# RPCamV2_Alt_camera_boardV2.net
KiCad netlist of a schematic drawn in EAGLE
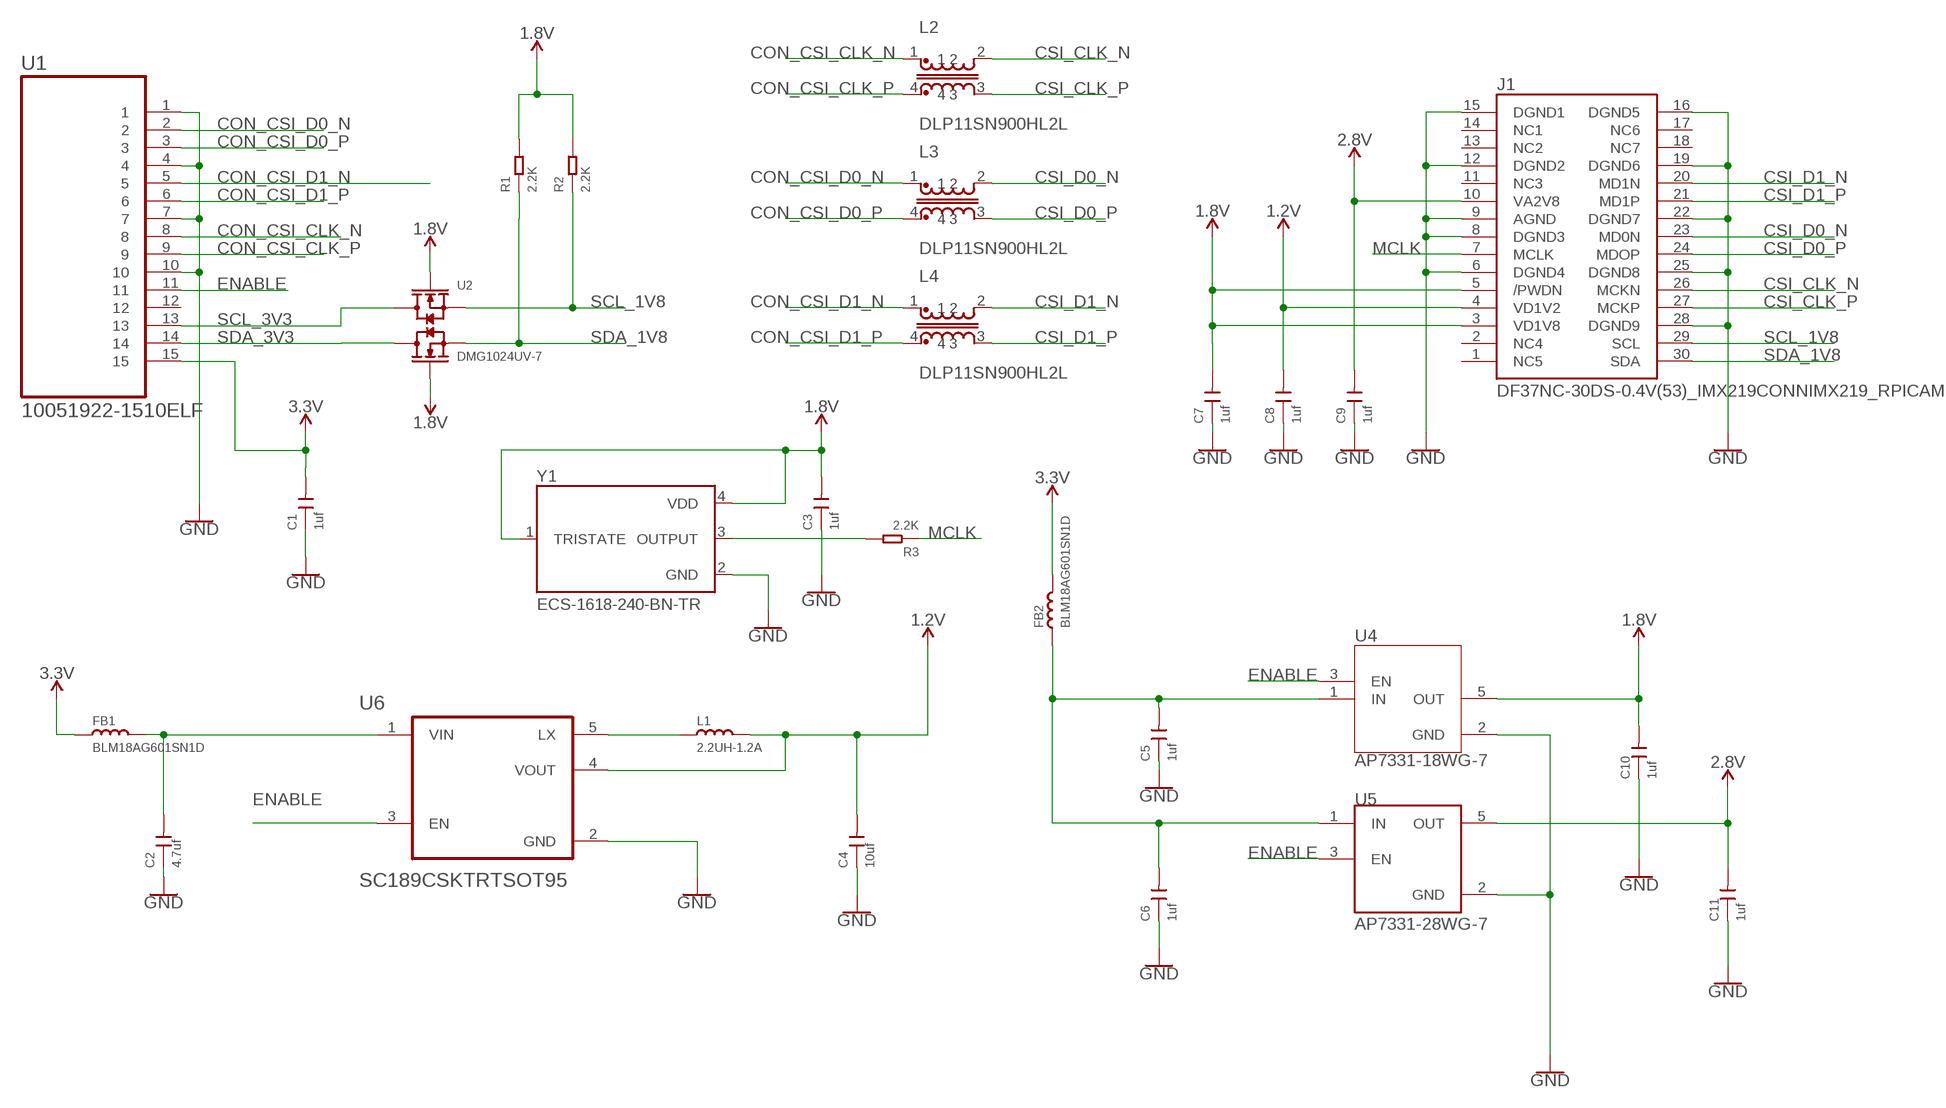
[diagram p0: schematic, sheet 1]

(export (version "E")
  (design (tool "Eeschema 10.0.6"))
  (components
    (comp (ref "C1")
      (value "1uf")
      (footprint "eagle-import:C0402K")
      (fields (field (name "MPN") "MF-CAP-0402-1uF"))
      (libsource (lib "eagle-import") (part "CERAMIC-1UF-10V-10%-X5R(0402)"))
    )
    (comp (ref "C2")
      (value "4.7uf")
      (footprint "eagle-import:C0603")
      (fields (field (name "MPN") "CC0603KRX5R6BB475"))
      (libsource (lib "eagle-import") (part "CERAMIC-4.7UF-10V-10%-X5R(0603)"))
    )
    (comp (ref "C3")
      (value "1uf")
      (footprint "eagle-import:C0402K")
      (fields (field (name "MPN") "MF-CAP-0402-1uF"))
      (libsource (lib "eagle-import") (part "CERAMIC-1UF-10V-10%-X5R(0402)"))
    )
    (comp (ref "C4")
      (value "10uf")
      (footprint "eagle-import:C2012")
      (fields (field (name "MPN") "CC0805KKX5R8BB106"))
      (libsource (lib "eagle-import") (part "CERAMIC-10UF-25V-10%-X5R(0805)"))
    )
    (comp (ref "C5")
      (value "1uf")
      (footprint "eagle-import:C0402K")
      (fields (field (name "MPN") "MF-CAP-0402-1uF"))
      (libsource (lib "eagle-import") (part "CERAMIC-1UF-10V-10%-X5R(0402)"))
    )
    (comp (ref "C6")
      (value "1uf")
      (footprint "eagle-import:C0402K")
      (fields (field (name "MPN") "MF-CAP-0402-1uF"))
      (libsource (lib "eagle-import") (part "CERAMIC-1UF-10V-10%-X5R(0402)"))
    )
    (comp (ref "C7")
      (value "1uf")
      (footprint "eagle-import:C0402K")
      (fields (field (name "MPN") "MF-CAP-0402-1uF"))
      (libsource (lib "eagle-import") (part "CERAMIC-1UF-10V-10%-X5R(0402)"))
    )
    (comp (ref "C8")
      (value "1uf")
      (footprint "eagle-import:C0402K")
      (fields (field (name "MPN") "MF-CAP-0402-1uF"))
      (libsource (lib "eagle-import") (part "CERAMIC-1UF-10V-10%-X5R(0402)"))
    )
    (comp (ref "C9")
      (value "1uf")
      (footprint "eagle-import:C0402K")
      (fields (field (name "MPN") "MF-CAP-0402-1uF"))
      (libsource (lib "eagle-import") (part "CERAMIC-1UF-10V-10%-X5R(0402)"))
    )
    (comp (ref "C10")
      (value "1uf")
      (footprint "eagle-import:C0402K")
      (fields (field (name "MPN") "MF-CAP-0402-1uF"))
      (libsource (lib "eagle-import") (part "CERAMIC-1UF-10V-10%-X5R(0402)"))
    )
    (comp (ref "C11")
      (value "1uf")
      (footprint "eagle-import:C0402K")
      (fields (field (name "MPN") "MF-CAP-0402-1uF"))
      (libsource (lib "eagle-import") (part "CERAMIC-1UF-10V-10%-X5R(0402)"))
    )
    (comp (ref "FB1")
      (value "BLM18AG601SN1D")
      (footprint "eagle-import:BEADC1608X80")
      (libsource (lib "eagle-import") (part "BLM18AG601SN1D"))
    )
    (comp (ref "FB2")
      (value "BLM18AG601SN1D")
      (footprint "eagle-import:BEADC1608X80")
      (libsource (lib "eagle-import") (part "BLM18AG601SN1D"))
    )
    (comp (ref "J1")
      (value "DF37NC-30DS-0.4V(53)_IMX219CONNIMX219_RPICAM")
      (footprint "eagle-import:HRS_DF37NC-30DS-0.4V(53)_IMX219")
      (fields (field (name "MPN") "DF37NC-30DS-0.4V(51)"))
      (libsource (lib "eagle-import") (part "DF37NC-30DS-0.4V(53)_IMX219CONNIMX219_RPICAM"))
    )
    (comp (ref "L1")
      (value "2.2UH-1.2A")
      (footprint "eagle-import:L0805")
      (fields (field (name "MPN") "LQM2MPN2R2MG0"))
      (libsource (lib "eagle-import") (part "SMD-INDUCTOR-2.2UH-20%-1.2A(0805)"))
    )
    (comp (ref "L2")
      (value "DLP11SN900HL2L")
      (footprint "eagle-import:INDC1210X09")
      (fields (field (name "MF") "Murata"))
      (libsource (lib "eagle-import") (part "DLP11SN900HL2L"))
    )
    (comp (ref "L3")
      (value "DLP11SN900HL2L")
      (footprint "eagle-import:INDC1210X09")
      (fields (field (name "MF") "Murata"))
      (libsource (lib "eagle-import") (part "DLP11SN900HL2L"))
    )
    (comp (ref "L4")
      (value "DLP11SN900HL2L")
      (footprint "eagle-import:INDC1210X09")
      (fields (field (name "MF") "Murata"))
      (libsource (lib "eagle-import") (part "DLP11SN900HL2L"))
    )
    (comp (ref "R1")
      (value "2.2K")
      (footprint "eagle-import:R0402")
      (fields (field (name "MPN") "RC0402JR-072K2L"))
      (libsource (lib "eagle-import") (part "SMD-RES-2.2K-5%-1/16W(0402)"))
    )
    (comp (ref "R2")
      (value "2.2K")
      (footprint "eagle-import:R0402")
      (fields (field (name "MPN") "RC0402JR-072K2L"))
      (libsource (lib "eagle-import") (part "SMD-RES-2.2K-5%-1/16W(0402)"))
    )
    (comp (ref "R3")
      (value "2.2K")
      (footprint "eagle-import:R0402")
      (fields (field (name "MPN") "RC0402JR-072K2L"))
      (libsource (lib "eagle-import") (part "SMD-RES-2.2K-5%-1/16W(0402)"))
    )
    (comp (ref "U1")
      (value "10051922-1510ELF")
      (footprint "eagle-import:FCI_10051922-1510ELF")
      (fields (field (name "MF") "FCI"))
      (libsource (lib "eagle-import") (part "10051922-1510ELF"))
    )
    (comp (ref "U2")
      (value "DMG1024UV-7")
      (footprint "eagle-import:SOT50P162X60-6N")
      (fields (field (name "MF") "Diodes Inc."))
      (libsource (lib "eagle-import") (part "DMG1024UV-7"))
    )
    (comp (ref "U4")
      (value "AP7331-18WG-7")
      (footprint "eagle-import:SOT95P285X145-5N")
      (fields (field (name "MF") "Diodes Inc."))
      (libsource (lib "eagle-import") (part "AP7331-18WG-7"))
    )
    (comp (ref "U5")
      (value "AP7331-28WG-7")
      (footprint "eagle-import:SOT95P285X145-5N")
      (fields (field (name "MF") "Diodes Inc."))
      (libsource (lib "eagle-import") (part "AP7331-28WG-7"))
    )
    (comp (ref "U6")
      (value "SC189CSKTRTSOT95")
      (footprint "eagle-import:SOT95P285X145-5N")
      (fields (field (name "MPN") "SC189CSKTRT"))
      (libsource (lib "eagle-import") (part "SC189CSKTRTSOT95"))
    )
    (comp (ref "Y1")
      (value "ECS-1618-240-BN-TR")
      (footprint "eagle-import:XTAL_ECS-1618-060-BN-TR")
      (fields (field (name "DIGI-KEY_PART_NUMBER") "XC1963CT-ND") (field (name "MF") "ECS International"))
      (libsource (lib "eagle-import") (part "ECS-1618-240-BN-TR"))
    )
  )
  (nets
    (net (code "1") (name "/CON_CSI_CLK_N") (class "Default")
      (node (ref "L2") (pin "1") (pinfunction "1_1") (pintype "passive"))
      (node (ref "U1") (pin "8") (pinfunction "8_8") (pintype "passive"))
    )
    (net (code "2") (name "/CON_CSI_CLK_P") (class "Default")
      (node (ref "L2") (pin "4") (pinfunction "4_4") (pintype "passive"))
      (node (ref "U1") (pin "9") (pinfunction "9_9") (pintype "passive"))
    )
    (net (code "3") (name "/CON_CSI_D0_N") (class "Default")
      (node (ref "L3") (pin "1") (pinfunction "1_1") (pintype "passive"))
      (node (ref "U1") (pin "2") (pinfunction "2_2") (pintype "passive"))
    )
    (net (code "4") (name "/CON_CSI_D0_P") (class "Default")
      (node (ref "L3") (pin "4") (pinfunction "4_4") (pintype "passive"))
      (node (ref "U1") (pin "3") (pinfunction "3_3") (pintype "passive"))
    )
    (net (code "5") (name "/CON_CSI_D1_N") (class "Default")
      (node (ref "L4") (pin "1") (pinfunction "1_1") (pintype "passive"))
      (node (ref "U1") (pin "5") (pinfunction "5_5") (pintype "passive"))
    )
    (net (code "6") (name "/CON_CSI_D1_P") (class "Default")
      (node (ref "L4") (pin "4") (pinfunction "4_4") (pintype "passive"))
      (node (ref "U1") (pin "6") (pinfunction "6_6") (pintype "passive"))
    )
    (net (code "7") (name "/CSI_CLK_N") (class "Default")
      (node (ref "J1") (pin "26") (pinfunction "MCKN_26") (pintype "passive"))
      (node (ref "L2") (pin "2") (pinfunction "2_2") (pintype "passive"))
    )
    (net (code "8") (name "/CSI_CLK_P") (class "Default")
      (node (ref "J1") (pin "27") (pinfunction "MCKP_27") (pintype "passive"))
      (node (ref "L2") (pin "3") (pinfunction "3_3") (pintype "passive"))
    )
    (net (code "9") (name "/CSI_D0_N") (class "Default")
      (node (ref "J1") (pin "23") (pinfunction "MD0N_23") (pintype "passive"))
      (node (ref "L3") (pin "2") (pinfunction "2_2") (pintype "passive"))
    )
    (net (code "10") (name "/CSI_D0_P") (class "Default")
      (node (ref "J1") (pin "24") (pinfunction "MDOP_24") (pintype "passive"))
      (node (ref "L3") (pin "3") (pinfunction "3_3") (pintype "passive"))
    )
    (net (code "11") (name "/CSI_D1_N") (class "Default")
      (node (ref "J1") (pin "20") (pinfunction "MD1N_20") (pintype "passive"))
      (node (ref "L4") (pin "2") (pinfunction "2_2") (pintype "passive"))
    )
    (net (code "12") (name "/CSI_D1_P") (class "Default")
      (node (ref "J1") (pin "21") (pinfunction "MD1P_21") (pintype "passive"))
      (node (ref "L4") (pin "3") (pinfunction "3_3") (pintype "passive"))
    )
    (net (code "13") (name "/ENABLE") (class "Default")
      (node (ref "U1") (pin "11") (pinfunction "11_11") (pintype "passive"))
      (node (ref "U4") (pin "3") (pinfunction "EN_3") (pintype "input"))
      (node (ref "U5") (pin "3") (pinfunction "EN_3") (pintype "input"))
      (node (ref "U6") (pin "3") (pinfunction "EN_3") (pintype "input"))
    )
    (net (code "14") (name "/MCLK") (class "Default")
      (node (ref "J1") (pin "7") (pinfunction "MCLK_7") (pintype "passive"))
      (node (ref "R3") (pin "1") (pinfunction "1_1") (pintype "passive"))
    )
    (net (code "15") (name "/SCL_1V8") (class "Default")
      (node (ref "J1") (pin "29") (pinfunction "SCL_29") (pintype "passive"))
      (node (ref "R2") (pin "1") (pinfunction "1_1") (pintype "passive"))
      (node (ref "U2") (pin "S2") (pinfunction "S1_S2") (pintype "passive"))
    )
    (net (code "16") (name "/SCL_3V3") (class "Default")
      (node (ref "U1") (pin "13") (pinfunction "13_13") (pintype "passive"))
      (node (ref "U2") (pin "D2") (pinfunction "D1_D2") (pintype "passive"))
    )
    (net (code "17") (name "/SDA_1V8") (class "Default")
      (node (ref "J1") (pin "30") (pinfunction "SDA_30") (pintype "passive"))
      (node (ref "R1") (pin "1") (pinfunction "1_1") (pintype "passive"))
      (node (ref "U2") (pin "S1") (pinfunction "S0_S1") (pintype "passive"))
    )
    (net (code "18") (name "/SDA_3V3") (class "Default")
      (node (ref "U1") (pin "14") (pinfunction "14_14") (pintype "passive"))
      (node (ref "U2") (pin "D1") (pinfunction "D0_D1") (pintype "passive"))
    )
    (net (code "19") (name "1.2V") (class "Default")
      (node (ref "C4") (pin "2") (pinfunction "2_2") (pintype "passive"))
      (node (ref "C8") (pin "2") (pinfunction "2_2") (pintype "passive"))
      (node (ref "J1") (pin "4") (pinfunction "VD1V2_4") (pintype "passive"))
      (node (ref "L1") (pin "2") (pinfunction "2_2") (pintype "passive"))
      (node (ref "U6") (pin "4") (pinfunction "VOUT_4") (pintype "power_in"))
    )
    (net (code "20") (name "1.8V") (class "Default")
      (node (ref "C10") (pin "2") (pinfunction "2_2") (pintype "passive"))
      (node (ref "C3") (pin "2") (pinfunction "2_2") (pintype "passive"))
      (node (ref "C7") (pin "2") (pinfunction "2_2") (pintype "passive"))
      (node (ref "J1") (pin "3") (pinfunction "VD1V8_3") (pintype "passive"))
      (node (ref "J1") (pin "5") (pinfunction "/PWDN_5") (pintype "passive"))
      (node (ref "R1") (pin "2") (pinfunction "2_2") (pintype "passive"))
      (node (ref "R2") (pin "2") (pinfunction "2_2") (pintype "passive"))
      (node (ref "U2") (pin "G1") (pinfunction "G0_G1") (pintype "passive"))
      (node (ref "U2") (pin "G2") (pinfunction "G1_G2") (pintype "passive"))
      (node (ref "U4") (pin "5") (pinfunction "OUT_5") (pintype "output"))
      (node (ref "Y1") (pin "1") (pinfunction "TRISTATE_1") (pintype "input"))
      (node (ref "Y1") (pin "4") (pinfunction "VDD_4") (pintype "power_in"))
    )
    (net (code "21") (name "2.8V") (class "Default")
      (node (ref "C11") (pin "2") (pinfunction "2_2") (pintype "passive"))
      (node (ref "C9") (pin "2") (pinfunction "2_2") (pintype "passive"))
      (node (ref "J1") (pin "10") (pinfunction "VA2V8_10") (pintype "passive"))
      (node (ref "U5") (pin "5") (pinfunction "OUT_5") (pintype "output"))
    )
    (net (code "22") (name "3.3V") (class "Default")
      (node (ref "C1") (pin "2") (pinfunction "2_2") (pintype "passive"))
      (node (ref "FB1") (pin "1") (pinfunction "1_1") (pintype "passive"))
      (node (ref "FB2") (pin "2") (pinfunction "2_2") (pintype "passive"))
      (node (ref "U1") (pin "15") (pinfunction "15_15") (pintype "passive"))
    )
    (net (code "23") (name "GND") (class "Default")
      (node (ref "C1") (pin "1") (pinfunction "1_1") (pintype "passive"))
      (node (ref "C10") (pin "1") (pinfunction "1_1") (pintype "passive"))
      (node (ref "C11") (pin "1") (pinfunction "1_1") (pintype "passive"))
      (node (ref "C2") (pin "1") (pinfunction "1_1") (pintype "passive"))
      (node (ref "C3") (pin "1") (pinfunction "1_1") (pintype "passive"))
      (node (ref "C4") (pin "1") (pinfunction "1_1") (pintype "passive"))
      (node (ref "C5") (pin "1") (pinfunction "1_1") (pintype "passive"))
      (node (ref "C6") (pin "1") (pinfunction "1_1") (pintype "passive"))
      (node (ref "C7") (pin "1") (pinfunction "1_1") (pintype "passive"))
      (node (ref "C8") (pin "1") (pinfunction "1_1") (pintype "passive"))
      (node (ref "C9") (pin "1") (pinfunction "1_1") (pintype "passive"))
      (node (ref "J1") (pin "12") (pinfunction "DGND2_12") (pintype "passive"))
      (node (ref "J1") (pin "15") (pinfunction "DGND1_15") (pintype "passive"))
      (node (ref "J1") (pin "16") (pinfunction "DGND5_16") (pintype "passive"))
      (node (ref "J1") (pin "19") (pinfunction "DGND6_19") (pintype "passive"))
      (node (ref "J1") (pin "22") (pinfunction "DGND7_22") (pintype "passive"))
      (node (ref "J1") (pin "25") (pinfunction "DGND8_25") (pintype "passive"))
      (node (ref "J1") (pin "28") (pinfunction "DGND9_28") (pintype "passive"))
      (node (ref "J1") (pin "6") (pinfunction "DGND4_6") (pintype "passive"))
      (node (ref "J1") (pin "8") (pinfunction "DGND3_8") (pintype "passive"))
      (node (ref "J1") (pin "9") (pinfunction "AGND_9") (pintype "passive"))
      (node (ref "U1") (pin "1") (pinfunction "1_1") (pintype "passive"))
      (node (ref "U1") (pin "10") (pinfunction "10_10") (pintype "passive"))
      (node (ref "U1") (pin "4") (pinfunction "4_4") (pintype "passive"))
      (node (ref "U1") (pin "7") (pinfunction "7_7") (pintype "passive"))
      (node (ref "U4") (pin "2") (pinfunction "GND_2") (pintype "power_in"))
      (node (ref "U5") (pin "2") (pinfunction "GND_2") (pintype "power_in"))
      (node (ref "U6") (pin "2") (pinfunction "GND_2") (pintype "power_in"))
      (node (ref "Y1") (pin "2") (pinfunction "GND_2") (pintype "power_in"))
    )
    (net (code "24") (name "Net-(U4-IN)") (class "Default")
      (node (ref "C5") (pin "2") (pinfunction "2_2") (pintype "passive"))
      (node (ref "C6") (pin "2") (pinfunction "2_2") (pintype "passive"))
      (node (ref "FB2") (pin "1") (pinfunction "1_1") (pintype "passive"))
      (node (ref "U4") (pin "1") (pinfunction "IN_1") (pintype "input"))
      (node (ref "U5") (pin "1") (pinfunction "IN_1") (pintype "input"))
    )
    (net (code "25") (name "Net-(U6-LX)") (class "Default")
      (node (ref "L1") (pin "1") (pinfunction "1_1") (pintype "passive"))
      (node (ref "U6") (pin "5") (pinfunction "LX_5") (pintype "power_in"))
    )
    (net (code "26") (name "Net-(U6-VIN)") (class "Default")
      (node (ref "C2") (pin "2") (pinfunction "2_2") (pintype "passive"))
      (node (ref "FB1") (pin "2") (pinfunction "2_2") (pintype "passive"))
      (node (ref "U6") (pin "1") (pinfunction "VIN_1") (pintype "power_in"))
    )
    (net (code "27") (name "Net-(Y1-OUTPUT)") (class "Default")
      (node (ref "R3") (pin "2") (pinfunction "2_2") (pintype "passive"))
      (node (ref "Y1") (pin "3") (pinfunction "OUTPUT_3") (pintype "output"))
    )
    (net (code "28") (name "unconnected-(J1-NC1-Pad14)") (class "Default")
      (node (ref "J1") (pin "14") (pinfunction "NC1_14") (pintype "passive"))
    )
    (net (code "29") (name "unconnected-(J1-NC2-Pad13)") (class "Default")
      (node (ref "J1") (pin "13") (pinfunction "NC2_13") (pintype "passive"))
    )
    (net (code "30") (name "unconnected-(J1-NC3-Pad11)") (class "Default")
      (node (ref "J1") (pin "11") (pinfunction "NC3_11") (pintype "passive"))
    )
    (net (code "31") (name "unconnected-(J1-NC4-Pad2)") (class "Default")
      (node (ref "J1") (pin "2") (pinfunction "NC4_2") (pintype "passive"))
    )
    (net (code "32") (name "unconnected-(J1-NC5-Pad1)") (class "Default")
      (node (ref "J1") (pin "1") (pinfunction "NC5_1") (pintype "passive"))
    )
    (net (code "33") (name "unconnected-(J1-NC6-Pad17)") (class "Default")
      (node (ref "J1") (pin "17") (pinfunction "NC6_17") (pintype "passive"))
    )
    (net (code "34") (name "unconnected-(J1-NC7-Pad18)") (class "Default")
      (node (ref "J1") (pin "18") (pinfunction "NC7_18") (pintype "passive"))
    )
    (net (code "35") (name "unconnected-(U1-Pad12)") (class "Default")
      (node (ref "U1") (pin "12") (pinfunction "12_12") (pintype "passive"))
    )
  )
)
